# GYRO_3-AXIS_-_ITG-3200.net
KiCad netlist of a schematic drawn in Altium Designer
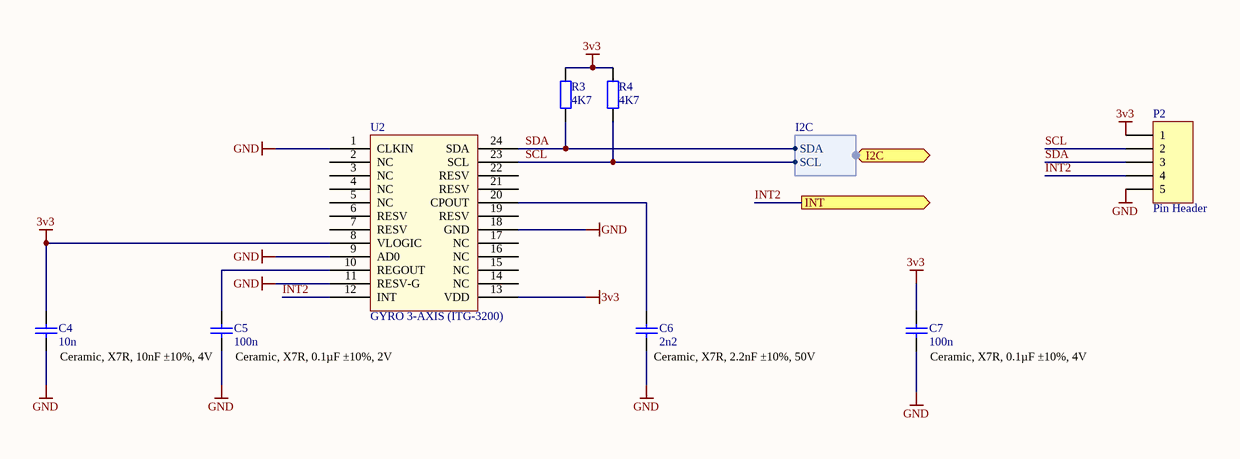
[diagram p0: GYRO 3-AXIS - ITG-3200.SchDoc]

(export (version "E")
  (design (tool "Eeschema 10.0.6"))
  (components
    (comp (ref "C4")
      (value "10n")
      (footprint "C0805")
      (fields (field (name "TOLERANCE") "0.1") (field (name "AUTHOR") "Willy Pietersz"))
      (libsource (lib "OurDb") (part "cap_NonPolar"))
    )
    (comp (ref "C5")
      (value "100n")
      (footprint "C0805")
      (fields (field (name "TOLERANCE") "0.1") (field (name "AUTHOR") "Willy Pietersz"))
      (libsource (lib "OurDb") (part "cap_NonPolar"))
    )
    (comp (ref "C6")
      (value "2n2")
      (footprint "C0805")
      (fields (field (name "TOLERANCE") "0.1") (field (name "AUTHOR") "Willy Pietersz"))
      (libsource (lib "OurDb") (part "cap_NonPolar"))
    )
    (comp (ref "C7")
      (value "100n")
      (footprint "C0805")
      (fields (field (name "TOLERANCE") "0.1") (field (name "AUTHOR") "Willy Pietersz"))
      (libsource (lib "OurDb") (part "cap_NonPolar"))
    )
    (comp (ref "P2")
      (value "Pin Header")
      (footprint "PH1x5_2.54")
      (description "Con1x5")
      (fields (field (name "PART NUMBER") "PH1x5") (field (name "AUTHOR") "Willy Pietersz"))
      (libsource (lib "OurDb") (part "Con1x5"))
    )
    (comp (ref "R3")
      (value "4K7")
      (footprint "R0805")
      (description "Resistor")
      (fields
        (field (name "POWER") "0.25W")
        (field (name "TOLERANCE") "0.05")
        (field (name "PUBLISHER") "Altium Limited")
        (field (name "AUTHOR") "Willy Pietersz")
      )
      (libsource (lib "OurDb") (part "RESISTOR"))
    )
    (comp (ref "R4")
      (value "4K7")
      (footprint "R0805")
      (description "Resistor")
      (fields
        (field (name "POWER") "0.25W")
        (field (name "TOLERANCE") "0.05")
        (field (name "PUBLISHER") "Altium Limited")
        (field (name "AUTHOR") "Willy Pietersz")
      )
      (libsource (lib "OurDb") (part "RESISTOR"))
    )
    (comp (ref "U2")
      (value "GYRO 3-AXIS (ITG-3200)")
      (footprint "QFN50P400X400-24V2M - GYRO 3axis")
      (description "Gyro, 3-axis")
      (fields (field (name "PART NUMBER") "ITG-3200"))
      (libsource (lib "OurDb") (part "ITG-3200"))
    )
  )
  (nets
    (net (code "2") (name "/INT2") (class "Default")
      (node (ref "P2") (pin "4") (pinfunction "4_4") (pintype "passive"))
      (node (ref "U2") (pin "12") (pinfunction "INT_12") (pintype "passive"))
    )
    (net (code "3") (name "/SCL") (class "Default")
      (node (ref "P2") (pin "2") (pinfunction "2_2") (pintype "passive"))
      (node (ref "R4") (pin "2") (pinfunction "2_2") (pintype "passive"))
      (node (ref "U2") (pin "23") (pinfunction "SCL_23") (pintype "passive"))
    )
    (net (code "4") (name "/SDA") (class "Default")
      (node (ref "P2") (pin "3") (pinfunction "3_3") (pintype "passive"))
      (node (ref "R3") (pin "2") (pinfunction "2_2") (pintype "passive"))
      (node (ref "U2") (pin "24") (pinfunction "SDA_24") (pintype "passive"))
    )
    (net (code "6") (name "3v3") (class "Default")
      (node (ref "C4") (pin "2") (pinfunction "2_2") (pintype "passive"))
      (node (ref "C7") (pin "2") (pinfunction "2_2") (pintype "passive"))
      (node (ref "P2") (pin "1") (pinfunction "1_1") (pintype "passive"))
      (node (ref "R3") (pin "1") (pinfunction "1_1") (pintype "passive"))
      (node (ref "R4") (pin "1") (pinfunction "1_1") (pintype "passive"))
      (node (ref "U2") (pin "13") (pinfunction "VDD_13") (pintype "passive"))
      (node (ref "U2") (pin "8") (pinfunction "VLOGIC_8") (pintype "passive"))
    )
    (net (code "7") (name "GND") (class "Default")
      (node (ref "C4") (pin "1") (pinfunction "1_1") (pintype "passive"))
      (node (ref "C5") (pin "1") (pinfunction "1_1") (pintype "passive"))
      (node (ref "C6") (pin "1") (pinfunction "1_1") (pintype "passive"))
      (node (ref "C7") (pin "1") (pinfunction "1_1") (pintype "passive"))
      (node (ref "P2") (pin "5") (pinfunction "5_5") (pintype "passive"))
      (node (ref "U2") (pin "1") (pinfunction "CLKIN_1") (pintype "passive"))
      (node (ref "U2") (pin "11") (pinfunction "RESV-G_11") (pintype "passive"))
      (node (ref "U2") (pin "18") (pinfunction "GND_18") (pintype "passive"))
      (node (ref "U2") (pin "9") (pinfunction "AD0_9") (pintype "passive"))
    )
    (net (code "8") (name "Net-(U2-CPOUT)") (class "Default")
      (node (ref "C6") (pin "2") (pinfunction "2_2") (pintype "passive"))
      (node (ref "U2") (pin "20") (pinfunction "CPOUT_20") (pintype "passive"))
    )
    (net (code "9") (name "Net-(U2-REGOUT)") (class "Default")
      (node (ref "C5") (pin "2") (pinfunction "2_2") (pintype "passive"))
      (node (ref "U2") (pin "10") (pinfunction "REGOUT_10") (pintype "passive"))
    )
    (net (code "10") (name "unconnected-(U2-NC-Pad2)") (class "Default")
      (node (ref "U2") (pin "2") (pinfunction "NC_2") (pintype "passive"))
    )
    (net (code "11") (name "unconnected-(U2-NC-Pad3)") (class "Default")
      (node (ref "U2") (pin "3") (pinfunction "NC_3") (pintype "passive"))
    )
    (net (code "12") (name "unconnected-(U2-NC-Pad4)") (class "Default")
      (node (ref "U2") (pin "4") (pinfunction "NC_4") (pintype "passive"))
    )
    (net (code "13") (name "unconnected-(U2-NC-Pad5)") (class "Default")
      (node (ref "U2") (pin "5") (pinfunction "NC_5") (pintype "passive"))
    )
    (net (code "14") (name "unconnected-(U2-NC-Pad14)") (class "Default")
      (node (ref "U2") (pin "14") (pinfunction "NC_14") (pintype "passive"))
    )
    (net (code "15") (name "unconnected-(U2-NC-Pad15)") (class "Default")
      (node (ref "U2") (pin "15") (pinfunction "NC_15") (pintype "passive"))
    )
    (net (code "16") (name "unconnected-(U2-NC-Pad16)") (class "Default")
      (node (ref "U2") (pin "16") (pinfunction "NC_16") (pintype "passive"))
    )
    (net (code "17") (name "unconnected-(U2-NC-Pad17)") (class "Default")
      (node (ref "U2") (pin "17") (pinfunction "NC_17") (pintype "passive"))
    )
    (net (code "18") (name "unconnected-(U2-RESV-Pad6)") (class "Default")
      (node (ref "U2") (pin "6") (pinfunction "RESV_6") (pintype "passive"))
    )
    (net (code "19") (name "unconnected-(U2-RESV-Pad7)") (class "Default")
      (node (ref "U2") (pin "7") (pinfunction "RESV_7") (pintype "passive"))
    )
    (net (code "20") (name "unconnected-(U2-RESV-Pad19)") (class "Default")
      (node (ref "U2") (pin "19") (pinfunction "RESV_19") (pintype "passive"))
    )
    (net (code "21") (name "unconnected-(U2-RESV-Pad21)") (class "Default")
      (node (ref "U2") (pin "21") (pinfunction "RESV_21") (pintype "passive"))
    )
    (net (code "22") (name "unconnected-(U2-RESV-Pad22)") (class "Default")
      (node (ref "U2") (pin "22") (pinfunction "RESV_22") (pintype "passive"))
    )
  )
)
